# BUCK_5v_TPS54340_P-MOS.net
KiCad netlist of a schematic drawn in Altium Designer
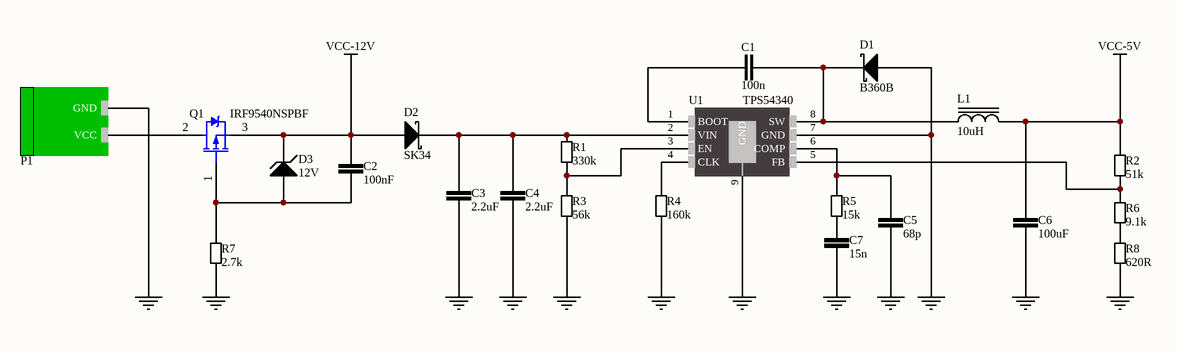
[diagram p0: BUCK_5v_TPS54340_P-MOS.SchDoc]

(export (version "E")
  (design (tool "Eeschema 10.0.6"))
  (components
    (comp (ref "C1")
      (value "100n")
      (footprint "CER_0603")
      (description "CAP CER 100n 10V X5R 10% 0603")
      (libsource (lib "Capacitors") (part "06032105"))
    )
    (comp (ref "C2")
      (value "100nF")
      (footprint "CER_0805")
      (description "CAP CER 100n 50V X7R 10% 0805")
      (libsource (lib "Capacitors") (part "00002105"))
    )
    (comp (ref "C3")
      (value "2.2uF")
      (footprint "CER_1210")
      (description "CAP CER 2.2u")
      (libsource (lib "Capacitors") (part "00001225"))
    )
    (comp (ref "C4")
      (value "2.2uF")
      (footprint "CER_1210")
      (description "CAP CER 2.2u")
      (libsource (lib "Capacitors") (part "00001225"))
    )
    (comp (ref "C5")
      (value "68p")
      (footprint "CER_0603")
      (description "CAP CER 68p 0603")
      (libsource (lib "Capacitors") (part "06032680"))
    )
    (comp (ref "C6")
      (value "100uF")
      (footprint "CER_1210")
      (description "CAP CER 100u X5R 6.3V 10% 1210")
      (libsource (lib "Capacitors") (part "00002108"))
    )
    (comp (ref "C7")
      (value "15n")
      (footprint "CER_0603")
      (description "CAP CER 15n 0603")
      (libsource (lib "Capacitors") (part "06032153"))
    )
    (comp (ref "D1")
      (value "B360B")
      (footprint "DO214AC")
      (description "DIODE SCHOTTKY 60V 3A DO214AC")
      (fields (field (name "MANUFACTURER") "Vishay Semiconductor Diodes Division"))
      (libsource (lib "Discrete_Semiconductor") (part "B360B"))
    )
    (comp (ref "D2")
      (value "SK34")
      (footprint "DO214AC")
      (description "DIODE SCHOTTKY 40V 3A DO214AC")
      (fields (field (name "MANUFACTURER") "Vishay Semiconductor Diodes Division"))
      (libsource (lib "Discrete_Semiconductor") (part "SK34"))
    )
    (comp (ref "D3")
      (value "12V")
      (footprint "DO214AC")
      (description "DIODE ZENER")
      (fields
        (field (name "MANUFACTURER") "Vishay Semiconductor Diodes Division")
        (field (name "MANUFACTURER PART NUMBER") "B360B")
      )
      (libsource (lib "Discrete_Semiconductor") (part "ZENER"))
    )
    (comp (ref "L1")
      (value "10uH")
      (footprint "INDUCTOR_SS1260-103MLD")
      (description "FIXED IND 10uH 5.3A")
      (fields
        (field (name "MANUFACTURER") "Coilcraft")
        (field (name "MANUFACTURER PART NUMBER") "XAL7030-103MEB")
      )
      (libsource (lib "Discrete_Semiconductor") (part "Inductor_10uH"))
    )
    (comp (ref "P1")
      (value "2EDGRC-5.08-02P-14-00A(H)")
      (footprint "PWR_Con")
      (description "TERM BLOCK HDR 2POS 90DEG 5.08MM")
      (libsource (lib "Electro_Mechanical") (part "00000002"))
    )
    (comp (ref "Q1")
      (value "IRF9540NSPBF")
      (footprint "D2PAK-2")
      (description "P-MOS")
      (fields (field (name "MANUFACTURER") "INTERNATIONAL RECTIFIER"))
      (libsource (lib "Discrete_Semiconductor") (part "IRF9540N"))
    )
    (comp (ref "R1")
      (value "330k")
      (footprint "RESC2013X38N-0805-NOOVERLAY")
      (description "RES SMD 330 kOhm 1/8W 0805")
      (fields (field (name "POWER") "0.125W, 1/8W"))
      (libsource (lib "Resistors") (part "00003303"))
    )
    (comp (ref "R2")
      (value "51k")
      (footprint "RESC2013X38N-0805-NOOVERLAY")
      (description "RES SMD 51 kOhm 1/8W 0805")
      (fields (field (name "POWER") "0.125W, 1/8W"))
      (libsource (lib "Resistors") (part "00005102"))
    )
    (comp (ref "R3")
      (value "56k")
      (footprint "RESC2013X38N-0805-NOOVERLAY")
      (description "RES SMD 56 kOhm 1/8W 0805")
      (fields (field (name "POWER") "0.125W, 1/8W"))
      (libsource (lib "Resistors") (part "00005602"))
    )
    (comp (ref "R4")
      (value "160k")
      (footprint "RESC2013X38N-0805-NOOVERLAY")
      (description "RES SMD 160 kOhm 1/8W 0805")
      (fields (field (name "POWER") "0.125W, 1/8W"))
      (libsource (lib "Resistors") (part "00001603"))
    )
    (comp (ref "R5")
      (value "15k")
      (footprint "RESC2013X38N-0805-NOOVERLAY")
      (description "RES SMD 15 kOhm 1/8W 0805")
      (fields (field (name "POWER") "0.125W, 1/8W"))
      (libsource (lib "Resistors") (part "00001502"))
    )
    (comp (ref "R6")
      (value "9.1k")
      (footprint "RESC2013X38N-0805-NOOVERLAY")
      (description "RES SMD 9.1 kOhm 1/8W 0805")
      (fields (field (name "POWER") "0.125W, 1/8W"))
      (libsource (lib "Resistors") (part "00009101"))
    )
    (comp (ref "R7")
      (value "2.7k")
      (footprint "RESC2013X38N-0805-NOOVERLAY")
      (description "RES SMD 2.7 kOhm 1/8W 0805")
      (fields (field (name "POWER") "0.125W, 1/8W"))
      (libsource (lib "Resistors") (part "00002701"))
    )
    (comp (ref "R8")
      (value "620R")
      (footprint "RESC2013X38N-0805-NOOVERLAY")
      (description "RES SMD 620 Ohm 1/8W 0805")
      (fields (field (name "POWER") "0.125W, 1/8W"))
      (libsource (lib "Resistors") (part "00006200"))
    )
    (comp (ref "U1")
      (value "TPS54340")
      (footprint "HSOP-8")
      (description "IC REG BUCK ADJ 3.5A 8SOPWRPAD")
      (libsource (lib "Integrated_circuits") (part "TPS54340"))
    )
  )
  (nets
    (net (code "1") (name "GND") (class "Default")
      (node (ref "C3") (pin "1") (pinfunction "1_1") (pintype "passive"))
      (node (ref "C4") (pin "1") (pinfunction "1_1") (pintype "passive"))
      (node (ref "C5") (pin "1") (pinfunction "1_1") (pintype "passive"))
      (node (ref "C6") (pin "1") (pinfunction "1_1") (pintype "passive"))
      (node (ref "C7") (pin "1") (pinfunction "1_1") (pintype "passive"))
      (node (ref "D1") (pin "2") (pinfunction "Anode_2") (pintype "passive"))
      (node (ref "P1") (pin "1") (pinfunction "GND_1") (pintype "passive"))
      (node (ref "R3") (pin "1") (pinfunction "1_1") (pintype "passive"))
      (node (ref "R4") (pin "1") (pinfunction "1_1") (pintype "passive"))
      (node (ref "R7") (pin "1") (pinfunction "1_1") (pintype "passive"))
      (node (ref "R8") (pin "1") (pinfunction "1_1") (pintype "passive"))
      (node (ref "U1") (pin "7") (pinfunction "GND_7") (pintype "passive"))
      (node (ref "U1") (pin "9") (pinfunction "GND_9") (pintype "passive"))
    )
    (net (code "2") (name "Net-(C7-Pad2)") (class "Default")
      (node (ref "C7") (pin "2") (pinfunction "2_2") (pintype "passive"))
      (node (ref "R5") (pin "1") (pinfunction "1_1") (pintype "passive"))
    )
    (net (code "3") (name "Net-(D1-Cathode)") (class "Default")
      (node (ref "C1") (pin "2") (pinfunction "2_2") (pintype "passive"))
      (node (ref "D1") (pin "1") (pinfunction "Cathode_1") (pintype "passive"))
      (node (ref "L1") (pin "1") (pinfunction "1_1") (pintype "passive"))
      (node (ref "U1") (pin "8") (pinfunction "SW_8") (pintype "passive"))
    )
    (net (code "4") (name "Net-(D2-Cathode)") (class "Default")
      (node (ref "C3") (pin "2") (pinfunction "2_2") (pintype "passive"))
      (node (ref "C4") (pin "2") (pinfunction "2_2") (pintype "passive"))
      (node (ref "D2") (pin "1") (pinfunction "Cathode_1") (pintype "passive"))
      (node (ref "R1") (pin "2") (pinfunction "2_2") (pintype "passive"))
      (node (ref "U1") (pin "2") (pinfunction "VIN_2") (pintype "passive"))
    )
    (net (code "5") (name "Net-(D3-Anode)") (class "Default")
      (node (ref "C2") (pin "1") (pinfunction "1_1") (pintype "passive"))
      (node (ref "D3") (pin "2") (pinfunction "Anode_2") (pintype "passive"))
      (node (ref "Q1") (pin "1") (pinfunction "G_1") (pintype "passive"))
      (node (ref "R7") (pin "2") (pinfunction "2_2") (pintype "passive"))
    )
    (net (code "6") (name "Net-(P1-VCC)") (class "Default")
      (node (ref "P1") (pin "2") (pinfunction "VCC_2") (pintype "passive"))
      (node (ref "Q1") (pin "2") (pinfunction "D_2") (pintype "passive"))
    )
    (net (code "7") (name "Net-(R6-Pad1)") (class "Default")
      (node (ref "R6") (pin "1") (pinfunction "1_1") (pintype "passive"))
      (node (ref "R8") (pin "2") (pinfunction "2_2") (pintype "passive"))
    )
    (net (code "8") (name "Net-(U1-BOOT)") (class "Default")
      (node (ref "C1") (pin "1") (pinfunction "1_1") (pintype "passive"))
      (node (ref "U1") (pin "1") (pinfunction "BOOT_1") (pintype "passive"))
    )
    (net (code "9") (name "Net-(U1-CLK)") (class "Default")
      (node (ref "R4") (pin "2") (pinfunction "2_2") (pintype "passive"))
      (node (ref "U1") (pin "4") (pinfunction "CLK_4") (pintype "passive"))
    )
    (net (code "10") (name "Net-(U1-COMP)") (class "Default")
      (node (ref "C5") (pin "2") (pinfunction "2_2") (pintype "passive"))
      (node (ref "R5") (pin "2") (pinfunction "2_2") (pintype "passive"))
      (node (ref "U1") (pin "6") (pinfunction "COMP_6") (pintype "passive"))
    )
    (net (code "11") (name "Net-(U1-EN)") (class "Default")
      (node (ref "R1") (pin "1") (pinfunction "1_1") (pintype "passive"))
      (node (ref "R3") (pin "2") (pinfunction "2_2") (pintype "passive"))
      (node (ref "U1") (pin "3") (pinfunction "EN_3") (pintype "passive"))
    )
    (net (code "12") (name "Net-(U1-FB)") (class "Default")
      (node (ref "R2") (pin "1") (pinfunction "1_1") (pintype "passive"))
      (node (ref "R6") (pin "2") (pinfunction "2_2") (pintype "passive"))
      (node (ref "U1") (pin "5") (pinfunction "FB_5") (pintype "passive"))
    )
    (net (code "13") (name "VCC-5V") (class "Default")
      (node (ref "C6") (pin "2") (pinfunction "2_2") (pintype "passive"))
      (node (ref "L1") (pin "2") (pinfunction "2_2") (pintype "passive"))
      (node (ref "R2") (pin "2") (pinfunction "2_2") (pintype "passive"))
    )
    (net (code "14") (name "VCC-12V") (class "Default")
      (node (ref "C2") (pin "2") (pinfunction "2_2") (pintype "passive"))
      (node (ref "D2") (pin "2") (pinfunction "Anode_2") (pintype "passive"))
      (node (ref "D3") (pin "1") (pinfunction "Cathode_1") (pintype "passive"))
      (node (ref "Q1") (pin "3") (pinfunction "S_3") (pintype "passive"))
    )
  )
)
